# backlight.net
KiCad netlist of a schematic drawn in EAGLE
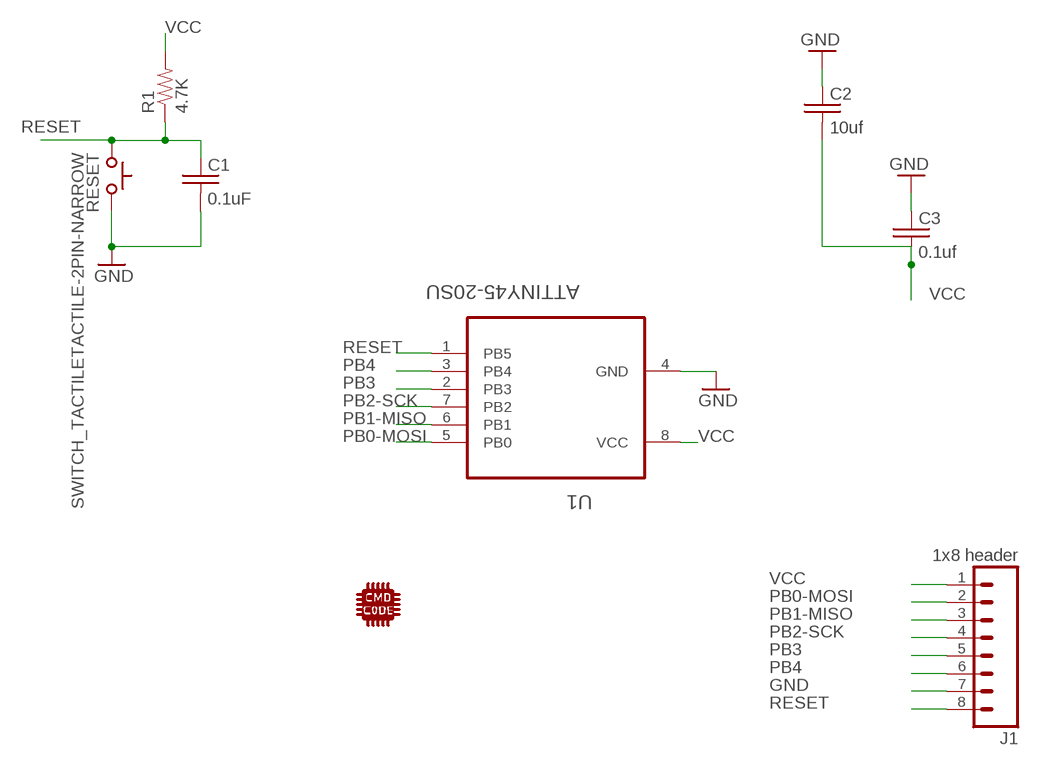
[diagram p0: schematic, sheet 1]
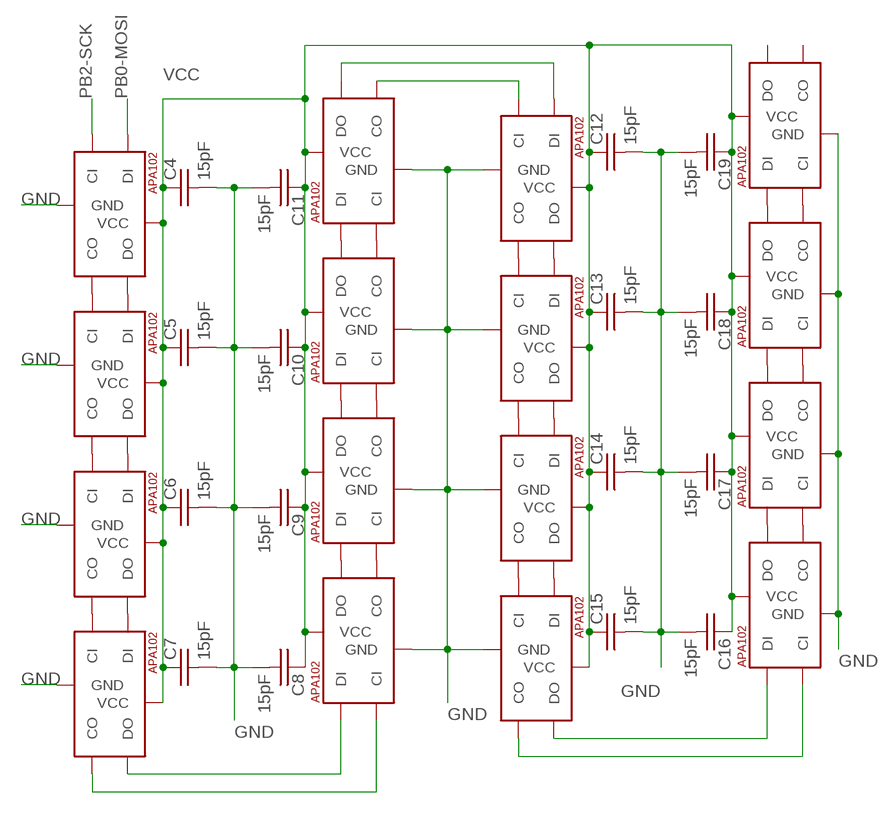
[diagram p1: schematic, sheet 2]

(export (version "E")
  (design (tool "Eeschema 10.0.6"))
  (components
    (comp (ref "C4")
      (value "15pF")
      (footprint "eagle-import:C0805K")
      (libsource (lib "eagle-import") (part "passives_C-USC0805K"))
    )
    (comp (ref "C5")
      (value "15pF")
      (footprint "eagle-import:C0805K")
      (libsource (lib "eagle-import") (part "passives_C-USC0805K"))
    )
    (comp (ref "C6")
      (value "15pF")
      (footprint "eagle-import:C0805K")
      (libsource (lib "eagle-import") (part "passives_C-USC0805K"))
    )
    (comp (ref "C7")
      (value "15pF")
      (footprint "eagle-import:C0805K")
      (libsource (lib "eagle-import") (part "passives_C-USC0805K"))
    )
    (comp (ref "C8")
      (value "15pF")
      (footprint "eagle-import:C0805K")
      (libsource (lib "eagle-import") (part "passives_C-USC0805K"))
    )
    (comp (ref "C9")
      (value "15pF")
      (footprint "eagle-import:C0805K")
      (libsource (lib "eagle-import") (part "passives_C-USC0805K"))
    )
    (comp (ref "C10")
      (value "15pF")
      (footprint "eagle-import:C0805K")
      (libsource (lib "eagle-import") (part "passives_C-USC0805K"))
    )
    (comp (ref "C11")
      (value "15pF")
      (footprint "eagle-import:C0805K")
      (libsource (lib "eagle-import") (part "passives_C-USC0805K"))
    )
    (comp (ref "C12")
      (value "15pF")
      (footprint "eagle-import:C0805K")
      (libsource (lib "eagle-import") (part "passives_C-USC0805K"))
    )
    (comp (ref "C13")
      (value "15pF")
      (footprint "eagle-import:C0805K")
      (libsource (lib "eagle-import") (part "passives_C-USC0805K"))
    )
    (comp (ref "C14")
      (value "15pF")
      (footprint "eagle-import:C0805K")
      (libsource (lib "eagle-import") (part "passives_C-USC0805K"))
    )
    (comp (ref "C15")
      (value "15pF")
      (footprint "eagle-import:C0805K")
      (libsource (lib "eagle-import") (part "passives_C-USC0805K"))
    )
    (comp (ref "C16")
      (value "15pF")
      (footprint "eagle-import:C0805K")
      (libsource (lib "eagle-import") (part "passives_C-USC0805K"))
    )
    (comp (ref "C17")
      (value "15pF")
      (footprint "eagle-import:C0805K")
      (libsource (lib "eagle-import") (part "passives_C-USC0805K"))
    )
    (comp (ref "C18")
      (value "15pF")
      (footprint "eagle-import:C0805K")
      (libsource (lib "eagle-import") (part "passives_C-USC0805K"))
    )
    (comp (ref "C19")
      (value "15pF")
      (footprint "eagle-import:C0805K")
      (libsource (lib "eagle-import") (part "passives_C-USC0805K"))
    )
    (comp (ref "U$1")
      (value "APA1025050")
      (footprint "eagle-import:APA102_5050")
      (libsource (lib "eagle-import") (part "APA1025050"))
    )
    (comp (ref "U$2")
      (value "APA1025050")
      (footprint "eagle-import:APA102_5050")
      (libsource (lib "eagle-import") (part "APA1025050"))
    )
    (comp (ref "U$3")
      (value "APA1025050")
      (footprint "eagle-import:APA102_5050")
      (libsource (lib "eagle-import") (part "APA1025050"))
    )
    (comp (ref "U$4")
      (value "APA1025050")
      (footprint "eagle-import:APA102_5050")
      (libsource (lib "eagle-import") (part "APA1025050"))
    )
    (comp (ref "U$5")
      (value "APA1025050")
      (footprint "eagle-import:APA102_5050")
      (libsource (lib "eagle-import") (part "APA1025050"))
    )
    (comp (ref "U$6")
      (value "APA1025050")
      (footprint "eagle-import:APA102_5050")
      (libsource (lib "eagle-import") (part "APA1025050"))
    )
    (comp (ref "U$7")
      (value "APA1025050")
      (footprint "eagle-import:APA102_5050")
      (libsource (lib "eagle-import") (part "APA1025050"))
    )
    (comp (ref "U$8")
      (value "APA1025050")
      (footprint "eagle-import:APA102_5050")
      (libsource (lib "eagle-import") (part "APA1025050"))
    )
    (comp (ref "U$9")
      (value "APA1025050")
      (footprint "eagle-import:APA102_5050")
      (libsource (lib "eagle-import") (part "APA1025050"))
    )
    (comp (ref "U$10")
      (value "APA1025050")
      (footprint "eagle-import:APA102_5050")
      (libsource (lib "eagle-import") (part "APA1025050"))
    )
    (comp (ref "U$11")
      (value "APA1025050")
      (footprint "eagle-import:APA102_5050")
      (libsource (lib "eagle-import") (part "APA1025050"))
    )
    (comp (ref "U$12")
      (value "APA1025050")
      (footprint "eagle-import:APA102_5050")
      (libsource (lib "eagle-import") (part "APA1025050"))
    )
    (comp (ref "U$13")
      (value "APA1025050")
      (footprint "eagle-import:APA102_5050")
      (libsource (lib "eagle-import") (part "APA1025050"))
    )
    (comp (ref "U$14")
      (value "APA1025050")
      (footprint "eagle-import:APA102_5050")
      (libsource (lib "eagle-import") (part "APA1025050"))
    )
    (comp (ref "U$15")
      (value "APA1025050")
      (footprint "eagle-import:APA102_5050")
      (libsource (lib "eagle-import") (part "APA1025050"))
    )
    (comp (ref "U$16")
      (value "APA1025050")
      (footprint "eagle-import:APA102_5050")
      (libsource (lib "eagle-import") (part "APA1025050"))
    )
    (comp (ref "C1")
      (value "0.1uF")
      (footprint "eagle-import:C0805K")
      (libsource (lib "eagle-import") (part "C-USC0805K"))
    )
    (comp (ref "C2")
      (value "10uf")
      (footprint "eagle-import:C0805K")
      (libsource (lib "eagle-import") (part "C-USC0805K"))
    )
    (comp (ref "C3")
      (value "0.1uf")
      (footprint "eagle-import:C0805K")
      (libsource (lib "eagle-import") (part "C-USC0805K"))
    )
    (comp (ref "J1")
      (value "1x8 header")
      (footprint "eagle-import:1X08")
      (libsource (lib "eagle-import") (part "M08SILK_FEMALE_PTH"))
    )
    (comp (ref "R1")
      (value "4.7K")
      (footprint "eagle-import:R0805")
      (libsource (lib "eagle-import") (part "RESISTORR0805-RES"))
    )
    (comp (ref "RESET")
      (value "SWITCH_TACTILETACTILE-2PIN-NARROW")
      (footprint "eagle-import:TACTILE-2PIN-NARROW")
      (libsource (lib "eagle-import") (part "SWITCH_TACTILETACTILE-2PIN-NARROW"))
    )
    (comp (ref "U$17")
      (value "CMD_C0DE_LOGOCMD_CODE_LOGO_TOP_COPPER")
      (footprint "eagle-import:CMD_C0DE_LOGO_TOP_COPPER")
      (libsource (lib "eagle-import") (part "CMD_C0DE_LOGOCMD_CODE_LOGO_TOP_COPPER"))
    )
    (comp (ref "U1")
      (value "ATTINY45-20SU")
      (footprint "eagle-import:SOIC127P798X216-8N")
      (fields (field (name "DIGI-KEY_PART_NUMBER") "ATTINY45-20SU-ND") (field (name "MF") "Microchip"))
      (libsource (lib "eagle-import") (part "ATTINY45-20SU"))
    )
  )
  (nets
    (net (code "1") (name "GND") (class "Default")
      (node (ref "C1") (pin "2") (pinfunction "2_2") (pintype "passive"))
      (node (ref "C10") (pin "2") (pinfunction "2_2") (pintype "passive"))
      (node (ref "C11") (pin "2") (pinfunction "2_2") (pintype "passive"))
      (node (ref "C12") (pin "2") (pinfunction "2_2") (pintype "passive"))
      (node (ref "C13") (pin "2") (pinfunction "2_2") (pintype "passive"))
      (node (ref "C14") (pin "2") (pinfunction "2_2") (pintype "passive"))
      (node (ref "C15") (pin "2") (pinfunction "2_2") (pintype "passive"))
      (node (ref "C16") (pin "2") (pinfunction "2_2") (pintype "passive"))
      (node (ref "C17") (pin "2") (pinfunction "2_2") (pintype "passive"))
      (node (ref "C18") (pin "2") (pinfunction "2_2") (pintype "passive"))
      (node (ref "C19") (pin "2") (pinfunction "2_2") (pintype "passive"))
      (node (ref "C2") (pin "1") (pinfunction "1_1") (pintype "passive"))
      (node (ref "C3") (pin "1") (pinfunction "1_1") (pintype "passive"))
      (node (ref "C4") (pin "2") (pinfunction "2_2") (pintype "passive"))
      (node (ref "C5") (pin "2") (pinfunction "2_2") (pintype "passive"))
      (node (ref "C6") (pin "2") (pinfunction "2_2") (pintype "passive"))
      (node (ref "C7") (pin "2") (pinfunction "2_2") (pintype "passive"))
      (node (ref "C8") (pin "2") (pinfunction "2_2") (pintype "passive"))
      (node (ref "C9") (pin "2") (pinfunction "2_2") (pintype "passive"))
      (node (ref "J1") (pin "7") (pinfunction "7_7") (pintype "passive"))
      (node (ref "RESET") (pin "P$1") (pinfunction "A_P$1") (pintype "passive"))
      (node (ref "U$1") (pin "6") (pinfunction "GND_6") (pintype "bidirectional"))
      (node (ref "U$10") (pin "6") (pinfunction "GND_6") (pintype "bidirectional"))
      (node (ref "U$11") (pin "6") (pinfunction "GND_6") (pintype "bidirectional"))
      (node (ref "U$12") (pin "6") (pinfunction "GND_6") (pintype "bidirectional"))
      (node (ref "U$13") (pin "6") (pinfunction "GND_6") (pintype "bidirectional"))
      (node (ref "U$14") (pin "6") (pinfunction "GND_6") (pintype "bidirectional"))
      (node (ref "U$15") (pin "6") (pinfunction "GND_6") (pintype "bidirectional"))
      (node (ref "U$16") (pin "6") (pinfunction "GND_6") (pintype "bidirectional"))
      (node (ref "U$2") (pin "6") (pinfunction "GND_6") (pintype "bidirectional"))
      (node (ref "U$3") (pin "6") (pinfunction "GND_6") (pintype "bidirectional"))
      (node (ref "U$4") (pin "6") (pinfunction "GND_6") (pintype "bidirectional"))
      (node (ref "U$5") (pin "6") (pinfunction "GND_6") (pintype "bidirectional"))
      (node (ref "U$6") (pin "6") (pinfunction "GND_6") (pintype "bidirectional"))
      (node (ref "U$7") (pin "6") (pinfunction "GND_6") (pintype "bidirectional"))
      (node (ref "U$8") (pin "6") (pinfunction "GND_6") (pintype "bidirectional"))
      (node (ref "U$9") (pin "6") (pinfunction "GND_6") (pintype "bidirectional"))
      (node (ref "U1") (pin "4") (pinfunction "GND_4") (pintype "passive"))
    )
    (net (code "2") (name "Net-(U$1-CO)") (class "Default")
      (node (ref "U$1") (pin "2") (pinfunction "CO_2") (pintype "bidirectional"))
      (node (ref "U$2") (pin "5") (pinfunction "CI_5") (pintype "bidirectional"))
    )
    (net (code "3") (name "Net-(U$1-DO)") (class "Default")
      (node (ref "U$1") (pin "3") (pinfunction "DO_3") (pintype "bidirectional"))
      (node (ref "U$2") (pin "4") (pinfunction "DI_4") (pintype "bidirectional"))
    )
    (net (code "4") (name "Net-(U$2-CO)") (class "Default")
      (node (ref "U$2") (pin "2") (pinfunction "CO_2") (pintype "bidirectional"))
      (node (ref "U$3") (pin "5") (pinfunction "CI_5") (pintype "bidirectional"))
    )
    (net (code "5") (name "Net-(U$2-DO)") (class "Default")
      (node (ref "U$2") (pin "3") (pinfunction "DO_3") (pintype "bidirectional"))
      (node (ref "U$3") (pin "4") (pinfunction "DI_4") (pintype "bidirectional"))
    )
    (net (code "6") (name "Net-(U$3-CO)") (class "Default")
      (node (ref "U$3") (pin "2") (pinfunction "CO_2") (pintype "bidirectional"))
      (node (ref "U$4") (pin "5") (pinfunction "CI_5") (pintype "bidirectional"))
    )
    (net (code "7") (name "Net-(U$3-DO)") (class "Default")
      (node (ref "U$3") (pin "3") (pinfunction "DO_3") (pintype "bidirectional"))
      (node (ref "U$4") (pin "4") (pinfunction "DI_4") (pintype "bidirectional"))
    )
    (net (code "8") (name "Net-(U$4-CO)") (class "Default")
      (node (ref "U$4") (pin "2") (pinfunction "CO_2") (pintype "bidirectional"))
      (node (ref "U$5") (pin "5") (pinfunction "CI_5") (pintype "bidirectional"))
    )
    (net (code "9") (name "Net-(U$4-DO)") (class "Default")
      (node (ref "U$4") (pin "3") (pinfunction "DO_3") (pintype "bidirectional"))
      (node (ref "U$5") (pin "4") (pinfunction "DI_4") (pintype "bidirectional"))
    )
    (net (code "10") (name "Net-(U$5-CO)") (class "Default")
      (node (ref "U$5") (pin "2") (pinfunction "CO_2") (pintype "bidirectional"))
      (node (ref "U$6") (pin "5") (pinfunction "CI_5") (pintype "bidirectional"))
    )
    (net (code "11") (name "Net-(U$5-DO)") (class "Default")
      (node (ref "U$5") (pin "3") (pinfunction "DO_3") (pintype "bidirectional"))
      (node (ref "U$6") (pin "4") (pinfunction "DI_4") (pintype "bidirectional"))
    )
    (net (code "12") (name "Net-(U$6-CO)") (class "Default")
      (node (ref "U$6") (pin "2") (pinfunction "CO_2") (pintype "bidirectional"))
      (node (ref "U$7") (pin "5") (pinfunction "CI_5") (pintype "bidirectional"))
    )
    (net (code "13") (name "Net-(U$6-DO)") (class "Default")
      (node (ref "U$6") (pin "3") (pinfunction "DO_3") (pintype "bidirectional"))
      (node (ref "U$7") (pin "4") (pinfunction "DI_4") (pintype "bidirectional"))
    )
    (net (code "14") (name "Net-(U$7-CO)") (class "Default")
      (node (ref "U$7") (pin "2") (pinfunction "CO_2") (pintype "bidirectional"))
      (node (ref "U$8") (pin "5") (pinfunction "CI_5") (pintype "bidirectional"))
    )
    (net (code "15") (name "Net-(U$7-DO)") (class "Default")
      (node (ref "U$7") (pin "3") (pinfunction "DO_3") (pintype "bidirectional"))
      (node (ref "U$8") (pin "4") (pinfunction "DI_4") (pintype "bidirectional"))
    )
    (net (code "16") (name "Net-(U$8-CO)") (class "Default")
      (node (ref "U$8") (pin "2") (pinfunction "CO_2") (pintype "bidirectional"))
      (node (ref "U$9") (pin "5") (pinfunction "CI_5") (pintype "bidirectional"))
    )
    (net (code "17") (name "Net-(U$8-DO)") (class "Default")
      (node (ref "U$8") (pin "3") (pinfunction "DO_3") (pintype "bidirectional"))
      (node (ref "U$9") (pin "4") (pinfunction "DI_4") (pintype "bidirectional"))
    )
    (net (code "18") (name "Net-(U$10-CI)") (class "Default")
      (node (ref "U$10") (pin "5") (pinfunction "CI_5") (pintype "bidirectional"))
      (node (ref "U$9") (pin "2") (pinfunction "CO_2") (pintype "bidirectional"))
    )
    (net (code "19") (name "Net-(U$10-CO)") (class "Default")
      (node (ref "U$10") (pin "2") (pinfunction "CO_2") (pintype "bidirectional"))
      (node (ref "U$11") (pin "5") (pinfunction "CI_5") (pintype "bidirectional"))
    )
    (net (code "20") (name "Net-(U$10-DI)") (class "Default")
      (node (ref "U$10") (pin "4") (pinfunction "DI_4") (pintype "bidirectional"))
      (node (ref "U$9") (pin "3") (pinfunction "DO_3") (pintype "bidirectional"))
    )
    (net (code "21") (name "Net-(U$10-DO)") (class "Default")
      (node (ref "U$10") (pin "3") (pinfunction "DO_3") (pintype "bidirectional"))
      (node (ref "U$11") (pin "4") (pinfunction "DI_4") (pintype "bidirectional"))
    )
    (net (code "22") (name "Net-(U$11-CO)") (class "Default")
      (node (ref "U$11") (pin "2") (pinfunction "CO_2") (pintype "bidirectional"))
      (node (ref "U$12") (pin "5") (pinfunction "CI_5") (pintype "bidirectional"))
    )
    (net (code "23") (name "Net-(U$11-DO)") (class "Default")
      (node (ref "U$11") (pin "3") (pinfunction "DO_3") (pintype "bidirectional"))
      (node (ref "U$12") (pin "4") (pinfunction "DI_4") (pintype "bidirectional"))
    )
    (net (code "24") (name "Net-(U$12-CO)") (class "Default")
      (node (ref "U$12") (pin "2") (pinfunction "CO_2") (pintype "bidirectional"))
      (node (ref "U$13") (pin "5") (pinfunction "CI_5") (pintype "bidirectional"))
    )
    (net (code "25") (name "Net-(U$12-DO)") (class "Default")
      (node (ref "U$12") (pin "3") (pinfunction "DO_3") (pintype "bidirectional"))
      (node (ref "U$13") (pin "4") (pinfunction "DI_4") (pintype "bidirectional"))
    )
    (net (code "26") (name "Net-(U$13-CO)") (class "Default")
      (node (ref "U$13") (pin "2") (pinfunction "CO_2") (pintype "bidirectional"))
      (node (ref "U$14") (pin "5") (pinfunction "CI_5") (pintype "bidirectional"))
    )
    (net (code "27") (name "Net-(U$13-DO)") (class "Default")
      (node (ref "U$13") (pin "3") (pinfunction "DO_3") (pintype "bidirectional"))
      (node (ref "U$14") (pin "4") (pinfunction "DI_4") (pintype "bidirectional"))
    )
    (net (code "28") (name "Net-(U$14-CO)") (class "Default")
      (node (ref "U$14") (pin "2") (pinfunction "CO_2") (pintype "bidirectional"))
      (node (ref "U$15") (pin "5") (pinfunction "CI_5") (pintype "bidirectional"))
    )
    (net (code "29") (name "Net-(U$14-DO)") (class "Default")
      (node (ref "U$14") (pin "3") (pinfunction "DO_3") (pintype "bidirectional"))
      (node (ref "U$15") (pin "4") (pinfunction "DI_4") (pintype "bidirectional"))
    )
    (net (code "30") (name "Net-(U$15-CO)") (class "Default")
      (node (ref "U$15") (pin "2") (pinfunction "CO_2") (pintype "bidirectional"))
      (node (ref "U$16") (pin "5") (pinfunction "CI_5") (pintype "bidirectional"))
    )
    (net (code "31") (name "Net-(U$15-DO)") (class "Default")
      (node (ref "U$15") (pin "3") (pinfunction "DO_3") (pintype "bidirectional"))
      (node (ref "U$16") (pin "4") (pinfunction "DI_4") (pintype "bidirectional"))
    )
    (net (code "32") (name "PB0-MOSI") (class "Default")
      (node (ref "J1") (pin "2") (pinfunction "2_2") (pintype "passive"))
      (node (ref "U$1") (pin "4") (pinfunction "DI_4") (pintype "bidirectional"))
      (node (ref "U1") (pin "5") (pinfunction "PB0_5") (pintype "bidirectional"))
    )
    (net (code "33") (name "PB1-MISO") (class "Default")
      (node (ref "J1") (pin "3") (pinfunction "3_3") (pintype "passive"))
      (node (ref "U1") (pin "6") (pinfunction "PB1_6") (pintype "bidirectional"))
    )
    (net (code "34") (name "PB2-SCK") (class "Default")
      (node (ref "J1") (pin "4") (pinfunction "4_4") (pintype "passive"))
      (node (ref "U$1") (pin "5") (pinfunction "CI_5") (pintype "bidirectional"))
      (node (ref "U1") (pin "7") (pinfunction "PB2_7") (pintype "bidirectional"))
    )
    (net (code "35") (name "PB3") (class "Default")
      (node (ref "J1") (pin "5") (pinfunction "5_5") (pintype "passive"))
      (node (ref "U1") (pin "2") (pinfunction "PB3_2") (pintype "bidirectional"))
    )
    (net (code "36") (name "PB4") (class "Default")
      (node (ref "J1") (pin "6") (pinfunction "6_6") (pintype "passive"))
      (node (ref "U1") (pin "3") (pinfunction "PB4_3") (pintype "bidirectional"))
    )
    (net (code "37") (name "RESET") (class "Default")
      (node (ref "C1") (pin "1") (pinfunction "1_1") (pintype "passive"))
      (node (ref "J1") (pin "8") (pinfunction "8_8") (pintype "passive"))
      (node (ref "R1") (pin "1") (pinfunction "1_1") (pintype "passive"))
      (node (ref "RESET") (pin "P$2") (pinfunction "C_P$2") (pintype "passive"))
      (node (ref "U1") (pin "1") (pinfunction "PB5_1") (pintype "bidirectional"))
    )
    (net (code "38") (name "VCC") (class "Default")
      (node (ref "C10") (pin "1") (pinfunction "1_1") (pintype "passive"))
      (node (ref "C11") (pin "1") (pinfunction "1_1") (pintype "passive"))
      (node (ref "C12") (pin "1") (pinfunction "1_1") (pintype "passive"))
      (node (ref "C13") (pin "1") (pinfunction "1_1") (pintype "passive"))
      (node (ref "C14") (pin "1") (pinfunction "1_1") (pintype "passive"))
      (node (ref "C15") (pin "1") (pinfunction "1_1") (pintype "passive"))
      (node (ref "C16") (pin "1") (pinfunction "1_1") (pintype "passive"))
      (node (ref "C17") (pin "1") (pinfunction "1_1") (pintype "passive"))
      (node (ref "C18") (pin "1") (pinfunction "1_1") (pintype "passive"))
      (node (ref "C19") (pin "1") (pinfunction "1_1") (pintype "passive"))
      (node (ref "C2") (pin "2") (pinfunction "2_2") (pintype "passive"))
      (node (ref "C3") (pin "2") (pinfunction "2_2") (pintype "passive"))
      (node (ref "C4") (pin "1") (pinfunction "1_1") (pintype "passive"))
      (node (ref "C5") (pin "1") (pinfunction "1_1") (pintype "passive"))
      (node (ref "C6") (pin "1") (pinfunction "1_1") (pintype "passive"))
      (node (ref "C7") (pin "1") (pinfunction "1_1") (pintype "passive"))
      (node (ref "C8") (pin "1") (pinfunction "1_1") (pintype "passive"))
      (node (ref "C9") (pin "1") (pinfunction "1_1") (pintype "passive"))
      (node (ref "J1") (pin "1") (pinfunction "1_1") (pintype "passive"))
      (node (ref "R1") (pin "2") (pinfunction "2_2") (pintype "passive"))
      (node (ref "U$1") (pin "1") (pinfunction "VCC_1") (pintype "bidirectional"))
      (node (ref "U$10") (pin "1") (pinfunction "VCC_1") (pintype "bidirectional"))
      (node (ref "U$11") (pin "1") (pinfunction "VCC_1") (pintype "bidirectional"))
      (node (ref "U$12") (pin "1") (pinfunction "VCC_1") (pintype "bidirectional"))
      (node (ref "U$13") (pin "1") (pinfunction "VCC_1") (pintype "bidirectional"))
      (node (ref "U$14") (pin "1") (pinfunction "VCC_1") (pintype "bidirectional"))
      (node (ref "U$15") (pin "1") (pinfunction "VCC_1") (pintype "bidirectional"))
      (node (ref "U$16") (pin "1") (pinfunction "VCC_1") (pintype "bidirectional"))
      (node (ref "U$2") (pin "1") (pinfunction "VCC_1") (pintype "bidirectional"))
      (node (ref "U$3") (pin "1") (pinfunction "VCC_1") (pintype "bidirectional"))
      (node (ref "U$4") (pin "1") (pinfunction "VCC_1") (pintype "bidirectional"))
      (node (ref "U$5") (pin "1") (pinfunction "VCC_1") (pintype "bidirectional"))
      (node (ref "U$6") (pin "1") (pinfunction "VCC_1") (pintype "bidirectional"))
      (node (ref "U$7") (pin "1") (pinfunction "VCC_1") (pintype "bidirectional"))
      (node (ref "U$8") (pin "1") (pinfunction "VCC_1") (pintype "bidirectional"))
      (node (ref "U$9") (pin "1") (pinfunction "VCC_1") (pintype "bidirectional"))
      (node (ref "U1") (pin "8") (pinfunction "VCC_8") (pintype "power_in"))
    )
    (net (code "39") (name "unconnected-(U$16-CO-Pad2)") (class "Default")
      (node (ref "U$16") (pin "2") (pinfunction "CO_2") (pintype "bidirectional"))
    )
    (net (code "40") (name "unconnected-(U$16-DO-Pad3)") (class "Default")
      (node (ref "U$16") (pin "3") (pinfunction "DO_3") (pintype "bidirectional"))
    )
  )
)
